# VGA_Blinken.net
KiCad netlist of a schematic drawn in EAGLE
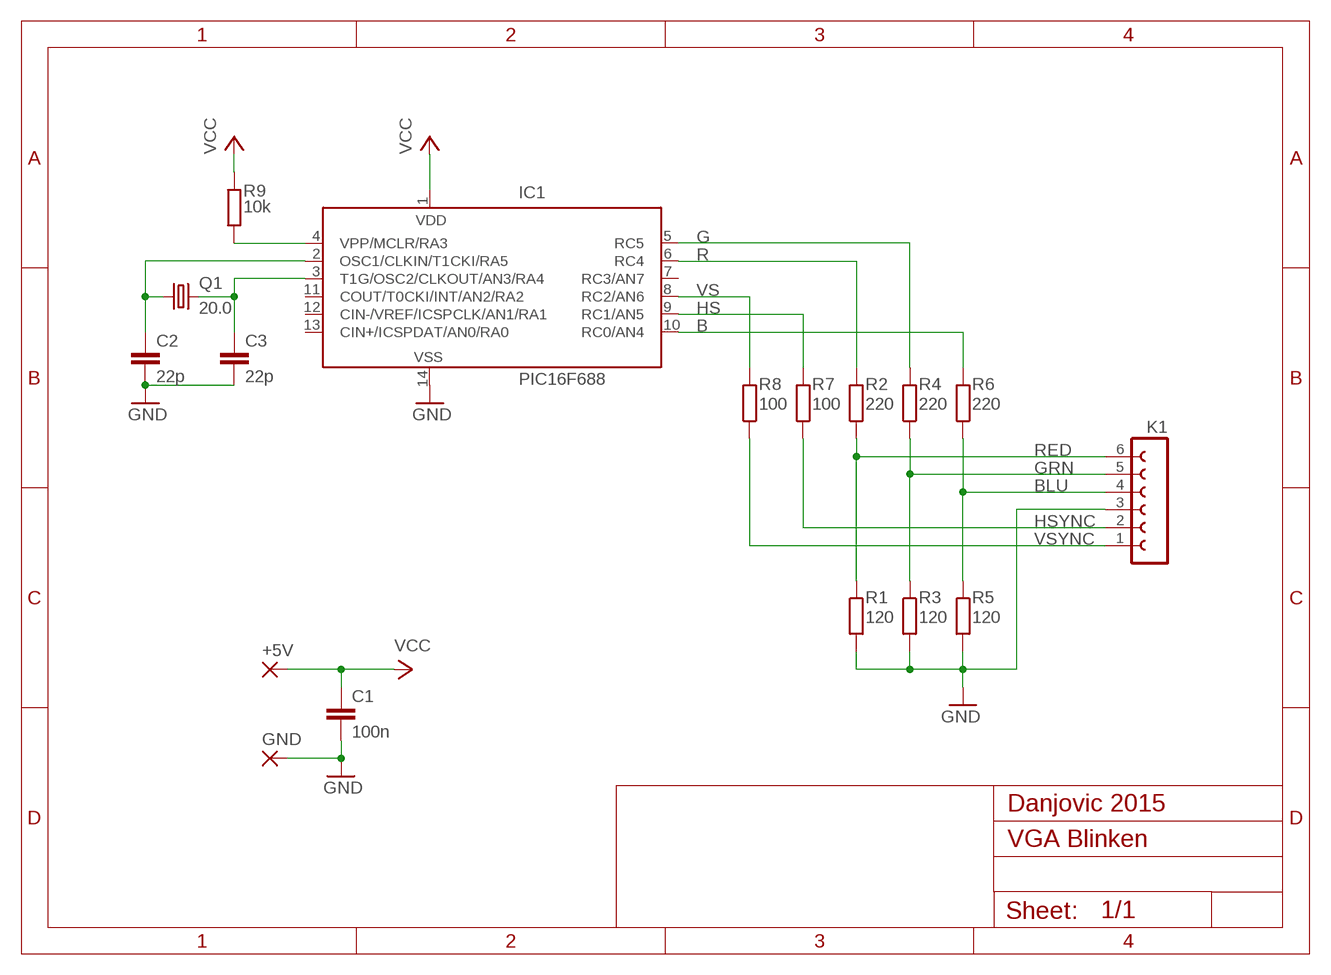
[diagram p0: schematic, sheet 1]

(export (version "E")
  (design (tool "Eeschema 10.0.6"))
  (components
    (comp (ref "+5V")
      (value "1,6/0,8")
      (footprint "eagle-import:1,6_0,8")
      (libsource (lib "eagle-import") (part "1,6/0,8"))
    )
    (comp (ref "C1")
      (value "100n")
      (footprint "eagle-import:C025-024X044L")
      (libsource (lib "eagle-import") (part "C-EU"))
    )
    (comp (ref "C2")
      (value "22p")
      (footprint "eagle-import:C025-024X044L")
      (libsource (lib "eagle-import") (part "C-EU"))
    )
    (comp (ref "C3")
      (value "22p")
      (footprint "eagle-import:C025-024X044L")
      (libsource (lib "eagle-import") (part "C-EU"))
    )
    (comp (ref "GND")
      (value "1,6/0,8")
      (footprint "eagle-import:1,6_0,8")
      (libsource (lib "eagle-import") (part "1,6/0,8"))
    )
    (comp (ref "IC1")
      (value "PIC16F688")
      (footprint "eagle-import:DIL14")
      (fields (field (name "MF") "MICROCHIP") (field (name "MPN") "PIC16F676-I/P"))
      (libsource (lib "eagle-import") (part "PIC16F676P"))
    )
    (comp (ref "K1")
      (value "FE06-1")
      (footprint "eagle-import:FE06")
      (libsource (lib "eagle-import") (part "FE06-1"))
    )
    (comp (ref "Q1")
      (value "20.0")
      (footprint "eagle-import:HC49_S")
      (libsource (lib "eagle-import") (part "CRYSTALHC49S"))
    )
    (comp (ref "R1")
      (value "120")
      (footprint "eagle-import:0204VL")
      (libsource (lib "eagle-import") (part "R-EU_0204/2VL"))
    )
    (comp (ref "R2")
      (value "220")
      (footprint "eagle-import:0204VL")
      (libsource (lib "eagle-import") (part "R-EU_0204/2VL"))
    )
    (comp (ref "R3")
      (value "120")
      (footprint "eagle-import:0204VL")
      (libsource (lib "eagle-import") (part "R-EU_0204/2VL"))
    )
    (comp (ref "R4")
      (value "220")
      (footprint "eagle-import:0204VL")
      (libsource (lib "eagle-import") (part "R-EU_0204/2VL"))
    )
    (comp (ref "R5")
      (value "120")
      (footprint "eagle-import:0204VL")
      (libsource (lib "eagle-import") (part "R-EU_0204/2VL"))
    )
    (comp (ref "R6")
      (value "220")
      (footprint "eagle-import:0204VL")
      (libsource (lib "eagle-import") (part "R-EU_0204/2VL"))
    )
    (comp (ref "R7")
      (value "100")
      (footprint "eagle-import:0204VL")
      (libsource (lib "eagle-import") (part "R-EU_0204/2VL"))
    )
    (comp (ref "R8")
      (value "100")
      (footprint "eagle-import:0204VL")
      (libsource (lib "eagle-import") (part "R-EU_0204/2VL"))
    )
    (comp (ref "R9")
      (value "10k")
      (footprint "eagle-import:0204VL")
      (libsource (lib "eagle-import") (part "R-EU_0204/2VL"))
    )
  )
  (nets
    (net (code "1") (name "/B") (class "Default")
      (node (ref "IC1") (pin "10") (pinfunction "RC0/AN4_10") (pintype "bidirectional"))
      (node (ref "R6") (pin "2") (pinfunction "2_2") (pintype "passive"))
    )
    (net (code "2") (name "/BLU") (class "Default")
      (node (ref "K1") (pin "4") (pinfunction "4_4") (pintype "passive"))
      (node (ref "R5") (pin "1") (pinfunction "1_1") (pintype "passive"))
      (node (ref "R6") (pin "1") (pinfunction "1_1") (pintype "passive"))
    )
    (net (code "3") (name "/G") (class "Default")
      (node (ref "IC1") (pin "5") (pinfunction "RC5_5") (pintype "bidirectional"))
      (node (ref "R4") (pin "2") (pinfunction "2_2") (pintype "passive"))
    )
    (net (code "4") (name "/GRN") (class "Default")
      (node (ref "K1") (pin "5") (pinfunction "5_5") (pintype "passive"))
      (node (ref "R3") (pin "1") (pinfunction "1_1") (pintype "passive"))
      (node (ref "R4") (pin "1") (pinfunction "1_1") (pintype "passive"))
    )
    (net (code "5") (name "/HS") (class "Default")
      (node (ref "IC1") (pin "9") (pinfunction "RC1/AN5_9") (pintype "bidirectional"))
      (node (ref "R7") (pin "2") (pinfunction "2_2") (pintype "passive"))
    )
    (net (code "6") (name "/HSYNC") (class "Default")
      (node (ref "K1") (pin "2") (pinfunction "2_2") (pintype "passive"))
      (node (ref "R7") (pin "1") (pinfunction "1_1") (pintype "passive"))
    )
    (net (code "7") (name "/R") (class "Default")
      (node (ref "IC1") (pin "6") (pinfunction "RC4_6") (pintype "bidirectional"))
      (node (ref "R2") (pin "2") (pinfunction "2_2") (pintype "passive"))
    )
    (net (code "8") (name "/RED") (class "Default")
      (node (ref "K1") (pin "6") (pinfunction "6_6") (pintype "passive"))
      (node (ref "R1") (pin "1") (pinfunction "1_1") (pintype "passive"))
      (node (ref "R2") (pin "1") (pinfunction "1_1") (pintype "passive"))
    )
    (net (code "9") (name "/VS") (class "Default")
      (node (ref "IC1") (pin "8") (pinfunction "RC2/AN6_8") (pintype "bidirectional"))
      (node (ref "R8") (pin "2") (pinfunction "2_2") (pintype "passive"))
    )
    (net (code "10") (name "/VSYNC") (class "Default")
      (node (ref "K1") (pin "1") (pinfunction "1_1") (pintype "passive"))
      (node (ref "R8") (pin "1") (pinfunction "1_1") (pintype "passive"))
    )
    (net (code "11") (name "GND") (class "Default")
      (node (ref "C1") (pin "2") (pinfunction "2_2") (pintype "passive"))
      (node (ref "C2") (pin "2") (pinfunction "2_2") (pintype "passive"))
      (node (ref "C3") (pin "2") (pinfunction "2_2") (pintype "passive"))
      (node (ref "GND") (pin "1") (pinfunction "P_1") (pintype "passive"))
      (node (ref "IC1") (pin "14") (pinfunction "VSS_14") (pintype "power_in"))
      (node (ref "K1") (pin "3") (pinfunction "3_3") (pintype "passive"))
      (node (ref "R1") (pin "2") (pinfunction "2_2") (pintype "passive"))
      (node (ref "R3") (pin "2") (pinfunction "2_2") (pintype "passive"))
      (node (ref "R5") (pin "2") (pinfunction "2_2") (pintype "passive"))
    )
    (net (code "12") (name "Net-(IC1-OSC1{slash}CLKIN{slash}T1CKI{slash}RA5)") (class "Default")
      (node (ref "C2") (pin "1") (pinfunction "1_1") (pintype "passive"))
      (node (ref "IC1") (pin "2") (pinfunction "OSC1/CLKIN/T1CKI/RA5_2") (pintype "bidirectional"))
      (node (ref "Q1") (pin "1") (pinfunction "1_1") (pintype "passive"))
    )
    (net (code "13") (name "Net-(IC1-T1G{slash}OSC2{slash}CLKOUT{slash}AN3{slash}RA4)") (class "Default")
      (node (ref "C3") (pin "1") (pinfunction "1_1") (pintype "passive"))
      (node (ref "IC1") (pin "3") (pinfunction "T1G/OSC2/CLKOUT/AN3/RA4_3") (pintype "bidirectional"))
      (node (ref "Q1") (pin "2") (pinfunction "2_2") (pintype "passive"))
    )
    (net (code "14") (name "Net-(IC1-VPP{slash}MCLR{slash}RA3)") (class "Default")
      (node (ref "IC1") (pin "4") (pinfunction "VPP/MCLR/RA3_4") (pintype "input"))
      (node (ref "R9") (pin "2") (pinfunction "2_2") (pintype "passive"))
    )
    (net (code "15") (name "VCC") (class "Default")
      (node (ref "+5V") (pin "1") (pinfunction "P_1") (pintype "passive"))
      (node (ref "C1") (pin "1") (pinfunction "1_1") (pintype "passive"))
      (node (ref "IC1") (pin "1") (pinfunction "VDD_1") (pintype "power_in"))
      (node (ref "R9") (pin "1") (pinfunction "1_1") (pintype "passive"))
    )
    (net (code "16") (name "unconnected-(IC1-CIN+{slash}ICSPDAT{slash}AN0{slash}RA0-Pad13)") (class "Default")
      (node (ref "IC1") (pin "13") (pinfunction "CIN+/ICSPDAT/AN0/RA0_13") (pintype "bidirectional"))
    )
    (net (code "17") (name "unconnected-(IC1-CIN-{slash}VREF{slash}ICSPCLK{slash}AN1{slash}RA1-Pad12)") (class "Default")
      (node (ref "IC1") (pin "12") (pinfunction "CIN-/VREF/ICSPCLK/AN1/RA1_12") (pintype "bidirectional"))
    )
    (net (code "18") (name "unconnected-(IC1-COUT{slash}T0CKI{slash}INT{slash}AN2{slash}RA2-Pad11)") (class "Default")
      (node (ref "IC1") (pin "11") (pinfunction "COUT/T0CKI/INT/AN2/RA2_11") (pintype "bidirectional"))
    )
    (net (code "19") (name "unconnected-(IC1-RC3{slash}AN7-Pad7)") (class "Default")
      (node (ref "IC1") (pin "7") (pinfunction "RC3/AN7_7") (pintype "bidirectional"))
    )
  )
)
